# lightboard.net
KiCad netlist of a schematic drawn in EAGLE
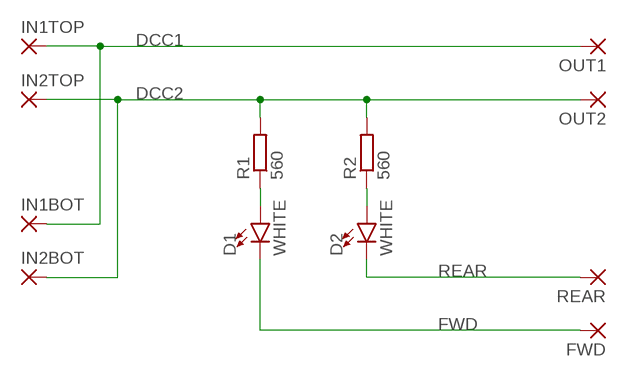
[diagram p0: schematic, sheet 1]

(export (version "E")
  (design (tool "Eeschema 10.0.6"))
  (components
    (comp (ref "D1")
      (value "WHITE")
      (footprint "eagle-import:LED-1206")
      (libsource (lib "eagle-import") (part "LED-WHITE1206"))
    )
    (comp (ref "D2")
      (value "WHITE")
      (footprint "eagle-import:LED-1206")
      (libsource (lib "eagle-import") (part "LED-WHITE1206"))
    )
    (comp (ref "FWD")
      (value "SMD2")
      (footprint "eagle-import:SMD1,27-2,54")
      (libsource (lib "eagle-import") (part "SMD2"))
    )
    (comp (ref "IN1BOT")
      (value "SMD2")
      (footprint "eagle-import:SMD1,27-2,54")
      (libsource (lib "eagle-import") (part "SMD2"))
    )
    (comp (ref "IN1TOP")
      (value "SMD2")
      (footprint "eagle-import:SMD1,27-2,54")
      (libsource (lib "eagle-import") (part "SMD2"))
    )
    (comp (ref "IN2BOT")
      (value "SMD2")
      (footprint "eagle-import:SMD1,27-2,54")
      (libsource (lib "eagle-import") (part "SMD2"))
    )
    (comp (ref "IN2TOP")
      (value "SMD2")
      (footprint "eagle-import:SMD1,27-2,54")
      (libsource (lib "eagle-import") (part "SMD2"))
    )
    (comp (ref "OUT1")
      (value "SMD2")
      (footprint "eagle-import:SMD1,27-2,54")
      (libsource (lib "eagle-import") (part "SMD2"))
    )
    (comp (ref "OUT2")
      (value "SMD2")
      (footprint "eagle-import:SMD1,27-2,54")
      (libsource (lib "eagle-import") (part "SMD2"))
    )
    (comp (ref "R1")
      (value "560")
      (footprint "eagle-import:R0603")
      (libsource (lib "eagle-import") (part "R-EU_R0603"))
    )
    (comp (ref "R2")
      (value "560")
      (footprint "eagle-import:R0603")
      (libsource (lib "eagle-import") (part "R-EU_R0603"))
    )
    (comp (ref "REAR")
      (value "SMD2")
      (footprint "eagle-import:SMD1,27-2,54")
      (libsource (lib "eagle-import") (part "SMD2"))
    )
  )
  (nets
    (net (code "1") (name "/DCC1") (class "Default")
      (node (ref "IN1BOT") (pin "1") (pinfunction "P_1") (pintype "passive"))
      (node (ref "IN1TOP") (pin "1") (pinfunction "P_1") (pintype "passive"))
      (node (ref "OUT1") (pin "1") (pinfunction "P_1") (pintype "passive"))
    )
    (net (code "2") (name "/DCC2") (class "Default")
      (node (ref "IN2BOT") (pin "1") (pinfunction "P_1") (pintype "passive"))
      (node (ref "IN2TOP") (pin "1") (pinfunction "P_1") (pintype "passive"))
      (node (ref "OUT2") (pin "1") (pinfunction "P_1") (pintype "passive"))
      (node (ref "R1") (pin "2") (pinfunction "2_2") (pintype "passive"))
      (node (ref "R2") (pin "2") (pinfunction "2_2") (pintype "passive"))
    )
    (net (code "3") (name "/FWD") (class "Default")
      (node (ref "D1") (pin "C") (pinfunction "C_C") (pintype "passive"))
      (node (ref "FWD") (pin "1") (pinfunction "P_1") (pintype "passive"))
    )
    (net (code "4") (name "/REAR") (class "Default")
      (node (ref "D2") (pin "C") (pinfunction "C_C") (pintype "passive"))
      (node (ref "REAR") (pin "1") (pinfunction "P_1") (pintype "passive"))
    )
    (net (code "5") (name "Net-(D1-PadA)") (class "Default")
      (node (ref "D1") (pin "A") (pinfunction "A_A") (pintype "passive"))
      (node (ref "R1") (pin "1") (pinfunction "1_1") (pintype "passive"))
    )
    (net (code "6") (name "Net-(D2-PadA)") (class "Default")
      (node (ref "D2") (pin "A") (pinfunction "A_A") (pintype "passive"))
      (node (ref "R2") (pin "1") (pinfunction "1_1") (pintype "passive"))
    )
  )
)
